# peripherals.net
KiCad netlist of a schematic drawn in Altium Designer
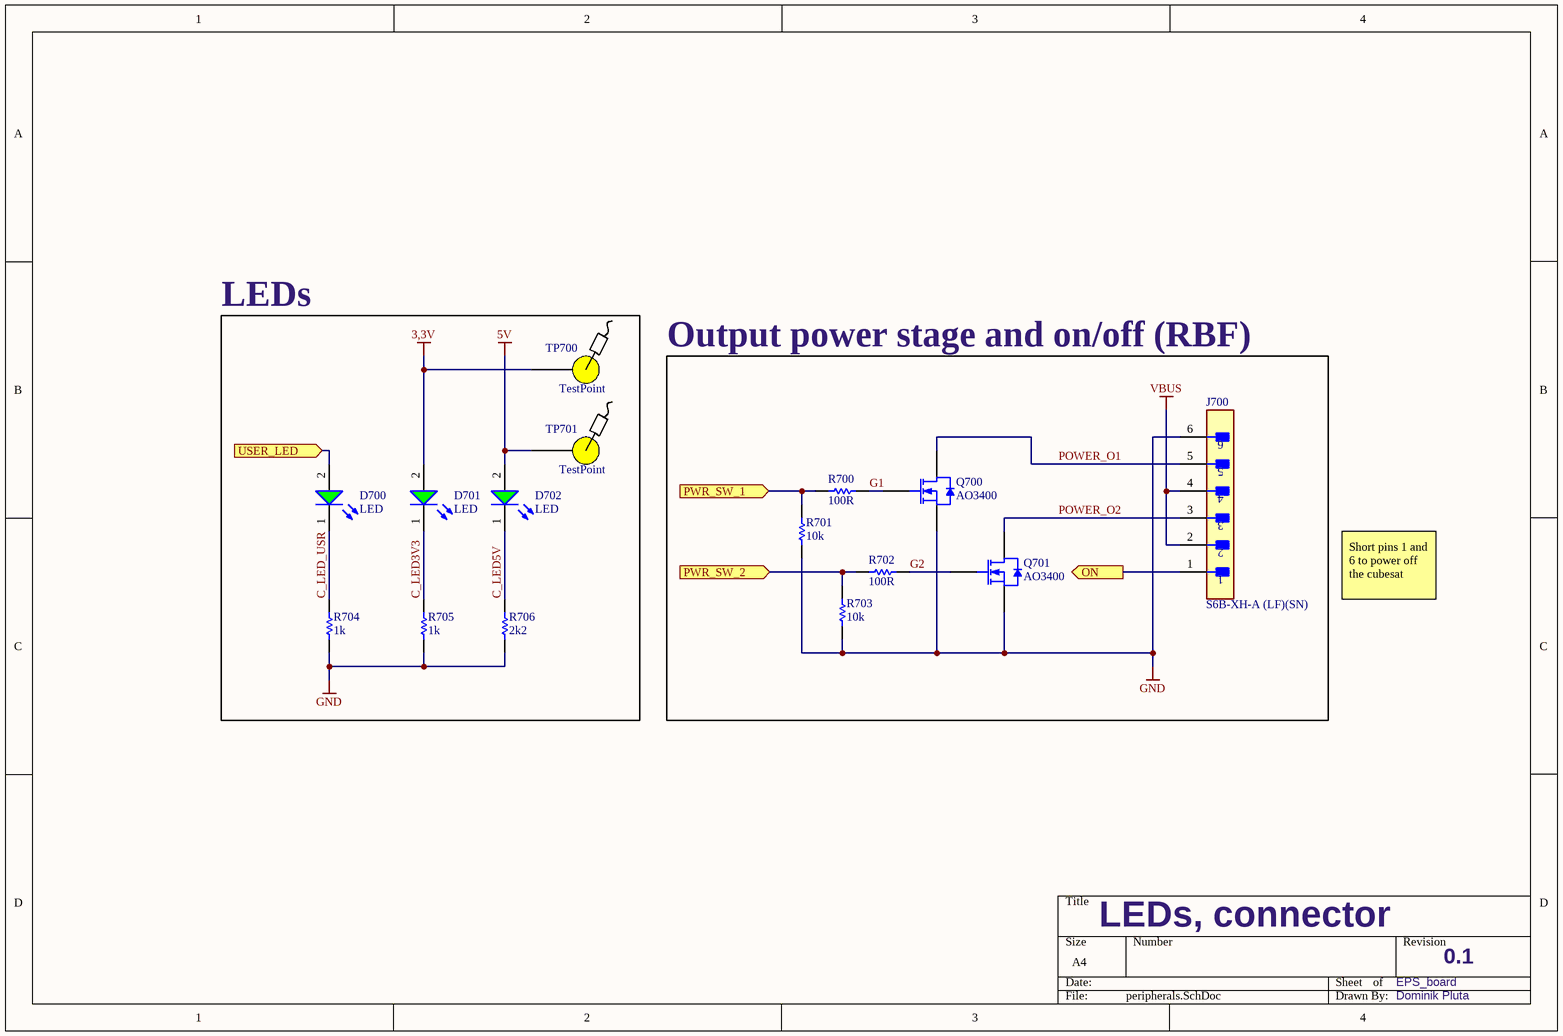
[diagram p0: peripherals.SchDoc]

(export (version "E")
  (design (tool "Eeschema 10.0.6"))
  (components
    (comp (ref "D700")
      (value "LED")
      (footprint "WL-SMCW_0603_150060xx75000")
      (description "Green LED")
      (libsource (lib "Altium Content Vault") (part "LED_Green_2A-1K"))
    )
    (comp (ref "D701")
      (value "LED")
      (footprint "WL-SMCW_0603_150060xx75000")
      (libsource (lib "Altium Content Vault") (part "LED_Green_2A-1K"))
    )
    (comp (ref "D702")
      (value "LED")
      (footprint "WL-SMCW_0603_150060xx75000")
      (libsource (lib "Altium Content Vault") (part "LED_Green_2A-1K"))
    )
    (comp (ref "J700")
      (value "S6B-XH-A (LF)(SN)")
      (footprint "FP-S6B-XH-A_LF_SN-MFG")
      (description "CONN HEADER R/A 6POS 2.5MM")
      (libsource (lib "Altium Content Vault") (part "f2cb566baf1c37ab5a3b8e90bbeafd6"))
    )
    (comp (ref "Q700")
      (value "AO3400")
      (footprint "AO-SOT23-3_V")
      (description "N-channel Enhancement Mode Field-Effect Transistor; 5.8A/30V")
      (fields (field (name "MANUFACTURER") "Alpha and Omega"))
      (libsource (lib "Altium Content Vault") (part "AO-NEMOS-G1S2D3-3"))
    )
    (comp (ref "Q701")
      (value "AO3400")
      (footprint "AO-SOT23-3_V")
      (description "N-channel Enhancement Mode Field-Effect Transistor; 5.8A/30V")
      (fields (field (name "MANUFACTURER") "Alpha and Omega"))
      (libsource (lib "Altium Content Vault") (part "AO-NEMOS-G1S2D3-3"))
    )
    (comp (ref "R700")
      (value "100R")
      (footprint "RESC0603(1608)_N")
      (description "100R 0.1W 5% 0603 SMD")
      (fields (field (name "TOLERANCE") "5 %") (field (name "POWER") "0.1 W"))
      (libsource (lib "Altium Content Vault") (part "RES"))
    )
    (comp (ref "R701")
      (value "10k")
      (footprint "RESC0603(1608)_N")
      (description "10k 0.1W 5% 0603 SMD")
      (fields (field (name "TOLERANCE") "5 %") (field (name "POWER") "0.1 W"))
      (libsource (lib "Altium Content Vault") (part "RES"))
    )
    (comp (ref "R702")
      (value "100R")
      (footprint "RESC0603(1608)_N")
      (description "100R 0.1W 5% 0603 SMD")
      (fields (field (name "TOLERANCE") "5 %") (field (name "POWER") "0.1 W"))
      (libsource (lib "Altium Content Vault") (part "RES"))
    )
    (comp (ref "R703")
      (value "10k")
      (footprint "RESC0603(1608)_N")
      (description "10k 0.1W 5% 0603 SMD")
      (fields (field (name "TOLERANCE") "5 %") (field (name "POWER") "0.1 W"))
      (libsource (lib "Altium Content Vault") (part "RES"))
    )
    (comp (ref "R704")
      (value "1k")
      (footprint "RESC0603(1608)_N")
      (description "1K 0.1W 5% 0603 SMD")
      (fields (field (name "TOLERANCE") "5 %") (field (name "POWER") "0.1 W"))
      (libsource (lib "Altium Content Vault") (part "RES"))
    )
    (comp (ref "R705")
      (value "1k")
      (footprint "RESC0603(1608)_N")
      (description "1k 0.1W 5% 0603 (1608 Metric)  SMD")
      (fields (field (name "TOLERANCE") "5 %") (field (name "POWER") "0.1 W"))
      (libsource (lib "Altium Content Vault") (part "RES"))
    )
    (comp (ref "R706")
      (value "2k2")
      (footprint "RESC0603(1608)_N")
      (description "2k2 0.1W 5% 0603 SMD")
      (fields (field (name "TOLERANCE") "5 %") (field (name "POWER") "0.1 W"))
      (libsource (lib "Altium Content Vault") (part "RES"))
    )
    (comp (ref "TP700")
      (value "TestPoint")
      (footprint "Test-point")
      (description "SMD test point")
      (libsource (lib "TestPoint") (part "Test-point"))
    )
    (comp (ref "TP701")
      (value "TestPoint")
      (footprint "Test-point")
      (description "SMD test point")
      (libsource (lib "TestPoint") (part "Test-point"))
    )
  )
  (nets
    (net (code "1") (name "/C_LED3V3") (class "Default")
      (node (ref "D701") (pin "1") (pinfunction "K_1") (pintype "passive"))
      (node (ref "R705") (pin "2") (pinfunction "2_2") (pintype "passive"))
    )
    (net (code "2") (name "/C_LED5V") (class "Default")
      (node (ref "D702") (pin "1") (pinfunction "K_1") (pintype "passive"))
      (node (ref "R706") (pin "2") (pinfunction "2_2") (pintype "passive"))
    )
    (net (code "3") (name "/C_LED_USR") (class "Default")
      (node (ref "D700") (pin "1") (pinfunction "K_1") (pintype "passive"))
      (node (ref "R704") (pin "2") (pinfunction "2_2") (pintype "passive"))
    )
    (net (code "4") (name "/G1") (class "Default")
      (node (ref "Q700") (pin "1") (pinfunction "G_1") (pintype "passive"))
      (node (ref "R700") (pin "1") (pinfunction "1_1") (pintype "passive"))
    )
    (net (code "5") (name "/G2") (class "Default")
      (node (ref "Q701") (pin "1") (pinfunction "G_1") (pintype "passive"))
      (node (ref "R702") (pin "1") (pinfunction "1_1") (pintype "passive"))
    )
    (net (code "6") (name "/ON") (class "Default")
      (node (ref "J700") (pin "1") (pinfunction "1_1") (pintype "passive"))
    )
    (net (code "7") (name "/POWER_O1") (class "Default")
      (node (ref "J700") (pin "5") (pinfunction "5_5") (pintype "passive"))
      (node (ref "Q700") (pin "3") (pinfunction "D_3") (pintype "passive"))
    )
    (net (code "8") (name "/POWER_O2") (class "Default")
      (node (ref "J700") (pin "3") (pinfunction "3_3") (pintype "passive"))
      (node (ref "Q701") (pin "3") (pinfunction "D_3") (pintype "passive"))
    )
    (net (code "9") (name "/PWR_SW_1") (class "Default")
      (node (ref "R700") (pin "2") (pinfunction "2_2") (pintype "passive"))
      (node (ref "R701") (pin "2") (pinfunction "2_2") (pintype "passive"))
    )
    (net (code "10") (name "/PWR_SW_2") (class "Default")
      (node (ref "R702") (pin "2") (pinfunction "2_2") (pintype "passive"))
      (node (ref "R703") (pin "2") (pinfunction "2_2") (pintype "passive"))
    )
    (net (code "11") (name "/USER_LED") (class "Default")
      (node (ref "D700") (pin "2") (pinfunction "A_2") (pintype "passive"))
    )
    (net (code "12") (name "3,3V") (class "Default")
      (node (ref "D701") (pin "2") (pinfunction "A_2") (pintype "passive"))
      (node (ref "TP700") (pin "1") (pintype "passive"))
    )
    (net (code "13") (name "5V") (class "Default")
      (node (ref "D702") (pin "2") (pinfunction "A_2") (pintype "passive"))
      (node (ref "TP701") (pin "1") (pintype "passive"))
    )
    (net (code "14") (name "GND") (class "Default")
      (node (ref "J700") (pin "6") (pinfunction "6_6") (pintype "passive"))
      (node (ref "Q700") (pin "2") (pinfunction "S_2") (pintype "passive"))
      (node (ref "Q701") (pin "2") (pinfunction "S_2") (pintype "passive"))
      (node (ref "R701") (pin "1") (pinfunction "1_1") (pintype "passive"))
      (node (ref "R703") (pin "1") (pinfunction "1_1") (pintype "passive"))
      (node (ref "R704") (pin "1") (pinfunction "1_1") (pintype "passive"))
      (node (ref "R705") (pin "1") (pinfunction "1_1") (pintype "passive"))
      (node (ref "R706") (pin "1") (pinfunction "1_1") (pintype "passive"))
    )
    (net (code "15") (name "VBUS") (class "Default")
      (node (ref "J700") (pin "2") (pinfunction "2_2") (pintype "passive"))
      (node (ref "J700") (pin "4") (pinfunction "4_4") (pintype "passive"))
    )
  )
)
